# power.net
KiCad netlist of a schematic drawn in EAGLE
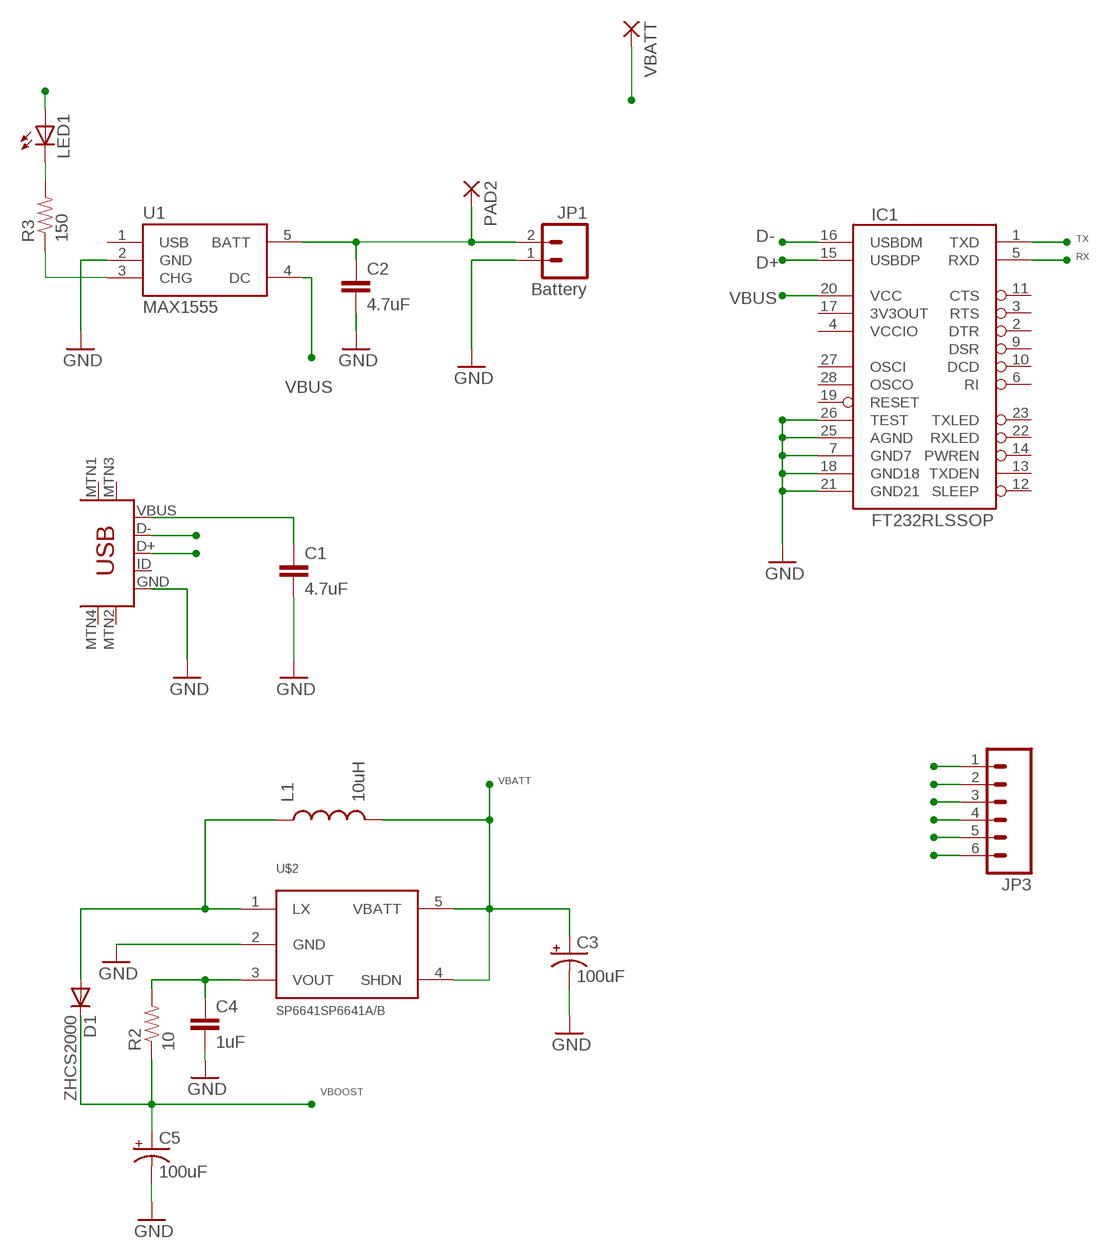
[diagram p0: schematic, sheet 1]

(export (version "E")
  (design (tool "Eeschema 10.0.6"))
  (components
    (comp (ref "C1")
      (value "4.7uF")
      (footprint "eagle-import:1206")
      (libsource (lib "eagle-import") (part "CAP1206"))
    )
    (comp (ref "C2")
      (value "4.7uF")
      (footprint "eagle-import:1206")
      (libsource (lib "eagle-import") (part "CAP1206"))
    )
    (comp (ref "C3")
      (value "100uF")
      (footprint "eagle-import:PANASONIC_D")
      (libsource (lib "eagle-import") (part "CPOL-USD"))
    )
    (comp (ref "C4")
      (value "1uF")
      (footprint "eagle-import:0805")
      (libsource (lib "eagle-import") (part "CAP0805"))
    )
    (comp (ref "C5")
      (value "100uF")
      (footprint "eagle-import:PANASONIC_D")
      (libsource (lib "eagle-import") (part "CPOL-USD"))
    )
    (comp (ref "D1")
      (value "ZHCS2000")
      (footprint "eagle-import:SMB-DIODE")
      (libsource (lib "eagle-import") (part "DIODESMB"))
    )
    (comp (ref "IC1")
      (value "FT232RLSSOP")
      (footprint "eagle-import:SSOP28DB")
      (libsource (lib "eagle-import") (part "FT232RLSSOP"))
    )
    (comp (ref "JP1")
      (value "Battery")
      (footprint "eagle-import:JST-2-SMD")
      (libsource (lib "eagle-import") (part "M02-JST-2MM-SMT"))
    )
    (comp (ref "JP3")
      (value "M06SMD")
      (footprint "eagle-import:1X06-SMD")
      (libsource (lib "eagle-import") (part "M06SMD"))
    )
    (comp (ref "L1")
      (value "10uH")
      (footprint "eagle-import:CR54")
      (libsource (lib "eagle-import") (part "INDUCTORCR54"))
    )
    (comp (ref "LED1")
      (value "LED0603")
      (footprint "eagle-import:LED-0603")
      (libsource (lib "eagle-import") (part "LED0603"))
    )
    (comp (ref "PAD2")
      (value "WIREPAD2,54/1,0")
      (footprint "eagle-import:2,54_1,0")
      (libsource (lib "eagle-import") (part "WIREPAD2,54/1,0"))
    )
    (comp (ref "R2")
      (value "10")
      (footprint "eagle-import:0603-RES")
      (libsource (lib "eagle-import") (part "RESISTOR0603-RES"))
    )
    (comp (ref "R3")
      (value "150")
      (footprint "eagle-import:0603-RES")
      (libsource (lib "eagle-import") (part "RESISTOR0603-RES"))
    )
    (comp (ref "U$1")
      (value "USB-MINIB-5PIN")
      (footprint "eagle-import:USB-MINIB")
      (libsource (lib "eagle-import") (part "USB-MINIB-5PIN"))
    )
    (comp (ref "U$2")
      (value "SP6641SP6641A/B")
      (footprint "eagle-import:SOT23-5")
      (libsource (lib "eagle-import") (part "SP6641SP6641A/B"))
    )
    (comp (ref "U1")
      (value "MAX1555")
      (footprint "eagle-import:SOT23-5")
      (libsource (lib "eagle-import") (part "MAX1555"))
    )
    (comp (ref "VBATT")
      (value "WIREPAD2,54/1,0")
      (footprint "eagle-import:2,54_1,0")
      (libsource (lib "eagle-import") (part "WIREPAD2,54/1,0"))
    )
  )
  (nets
    (net (code "1") (name "/D+") (class "Default")
      (node (ref "IC1") (pin "15") (pinfunction "USBDP_15") (pintype "bidirectional"))
      (node (ref "U$1") (pin "D+") (pinfunction "D+_D+") (pintype "bidirectional"))
    )
    (net (code "2") (name "/D-") (class "Default")
      (node (ref "IC1") (pin "16") (pinfunction "USBDM_16") (pintype "bidirectional"))
      (node (ref "U$1") (pin "D-") (pinfunction "D-_D-") (pintype "bidirectional"))
    )
    (net (code "3") (name "/RX") (class "Default")
      (node (ref "IC1") (pin "5") (pinfunction "RXD_5") (pintype "input"))
      (node (ref "JP3") (pin "1") (pinfunction "1_1") (pintype "passive"))
    )
    (net (code "4") (name "/TX") (class "Default")
      (node (ref "IC1") (pin "1") (pinfunction "TXD_1") (pintype "output"))
      (node (ref "JP3") (pin "2") (pinfunction "2_2") (pintype "passive"))
    )
    (net (code "5") (name "/VBATT") (class "Default")
      (node (ref "C3") (pin "+") (pinfunction "+_+") (pintype "passive"))
      (node (ref "JP3") (pin "5") (pinfunction "5_5") (pintype "passive"))
      (node (ref "L1") (pin "P$2") (pinfunction "2_P$2") (pintype "passive"))
      (node (ref "U$2") (pin "4") (pinfunction "SHDN_4") (pintype "bidirectional"))
      (node (ref "U$2") (pin "5") (pinfunction "VBATT_5") (pintype "bidirectional"))
      (node (ref "VBATT") (pin "1") (pinfunction "P_1") (pintype "passive"))
    )
    (net (code "6") (name "/VBOOST") (class "Default")
      (node (ref "C5") (pin "+") (pinfunction "+_+") (pintype "passive"))
      (node (ref "D1") (pin "C") (pinfunction "C_C") (pintype "passive"))
      (node (ref "JP3") (pin "4") (pinfunction "4_4") (pintype "passive"))
      (node (ref "R2") (pin "1") (pinfunction "1_1") (pintype "passive"))
    )
    (net (code "7") (name "/VBUS") (class "Default")
      (node (ref "C1") (pin "1") (pinfunction "1_1") (pintype "passive"))
      (node (ref "IC1") (pin "20") (pinfunction "VCC_20") (pintype "power_in"))
      (node (ref "JP3") (pin "3") (pinfunction "3_3") (pintype "passive"))
      (node (ref "LED1") (pin "A") (pinfunction "A_A") (pintype "passive"))
      (node (ref "U$1") (pin "VBUS") (pinfunction "VBUS_VBUS") (pintype "bidirectional"))
      (node (ref "U1") (pin "4") (pinfunction "DC_4") (pintype "bidirectional"))
    )
    (net (code "8") (name "/VCCIO") (class "Default")
      (node (ref "IC1") (pin "4") (pinfunction "VCCIO_4") (pintype "power_in"))
    )
    (net (code "9") (name "GND") (class "Default")
      (node (ref "C1") (pin "2") (pinfunction "2_2") (pintype "passive"))
      (node (ref "C2") (pin "2") (pinfunction "2_2") (pintype "passive"))
      (node (ref "C3") (pin "-") (pinfunction "-_-") (pintype "passive"))
      (node (ref "C4") (pin "2") (pinfunction "2_2") (pintype "passive"))
      (node (ref "C5") (pin "-") (pinfunction "-_-") (pintype "passive"))
      (node (ref "IC1") (pin "18") (pinfunction "GND18_18") (pintype "power_in"))
      (node (ref "IC1") (pin "21") (pinfunction "GND21_21") (pintype "power_in"))
      (node (ref "IC1") (pin "25") (pinfunction "AGND_25") (pintype "power_in"))
      (node (ref "IC1") (pin "26") (pinfunction "TEST_26") (pintype "input"))
      (node (ref "IC1") (pin "7") (pinfunction "GND7_7") (pintype "power_in"))
      (node (ref "JP1") (pin "1") (pinfunction "1_1") (pintype "passive"))
      (node (ref "JP3") (pin "6") (pinfunction "6_6") (pintype "passive"))
      (node (ref "U$1") (pin "GND") (pinfunction "GND_GND") (pintype "bidirectional"))
      (node (ref "U$2") (pin "2") (pinfunction "GND_2") (pintype "bidirectional"))
      (node (ref "U1") (pin "2") (pinfunction "GND_2") (pintype "bidirectional"))
    )
    (net (code "10") (name "Net-(L1-1)") (class "Default")
      (node (ref "D1") (pin "A") (pinfunction "A_A") (pintype "passive"))
      (node (ref "L1") (pin "P$1") (pinfunction "1_P$1") (pintype "passive"))
      (node (ref "U$2") (pin "1") (pinfunction "LX_1") (pintype "bidirectional"))
    )
    (net (code "11") (name "Net-(LED1-PadC)") (class "Default")
      (node (ref "LED1") (pin "C") (pinfunction "C_C") (pintype "passive"))
      (node (ref "R3") (pin "2") (pinfunction "2_2") (pintype "passive"))
    )
    (net (code "12") (name "Net-(PAD2-P)") (class "Default")
      (node (ref "C2") (pin "1") (pinfunction "1_1") (pintype "passive"))
      (node (ref "JP1") (pin "2") (pinfunction "2_2") (pintype "passive"))
      (node (ref "PAD2") (pin "1") (pinfunction "P_1") (pintype "passive"))
      (node (ref "U1") (pin "5") (pinfunction "BATT_5") (pintype "bidirectional"))
    )
    (net (code "13") (name "Net-(U$2-VOUT)") (class "Default")
      (node (ref "C4") (pin "1") (pinfunction "1_1") (pintype "passive"))
      (node (ref "R2") (pin "2") (pinfunction "2_2") (pintype "passive"))
      (node (ref "U$2") (pin "3") (pinfunction "VOUT_3") (pintype "bidirectional"))
    )
    (net (code "14") (name "Net-(U1-CHG)") (class "Default")
      (node (ref "R3") (pin "1") (pinfunction "1_1") (pintype "passive"))
      (node (ref "U1") (pin "3") (pinfunction "CHG_3") (pintype "bidirectional"))
    )
    (net (code "15") (name "unconnected-(IC1-3V3OUT-Pad17)") (class "Default")
      (node (ref "IC1") (pin "17") (pinfunction "3V3OUT_17") (pintype "output"))
    )
    (net (code "16") (name "unconnected-(IC1-CTS-Pad11)") (class "Default")
      (node (ref "IC1") (pin "11") (pinfunction "CTS_11") (pintype "input"))
    )
    (net (code "17") (name "unconnected-(IC1-DCD-Pad10)") (class "Default")
      (node (ref "IC1") (pin "10") (pinfunction "DCD_10") (pintype "input"))
    )
    (net (code "18") (name "unconnected-(IC1-DSR-Pad9)") (class "Default")
      (node (ref "IC1") (pin "9") (pinfunction "DSR_9") (pintype "input"))
    )
    (net (code "19") (name "unconnected-(IC1-DTR-Pad2)") (class "Default")
      (node (ref "IC1") (pin "2") (pinfunction "DTR_2") (pintype "output"))
    )
    (net (code "20") (name "unconnected-(IC1-OSCI-Pad27)") (class "Default")
      (node (ref "IC1") (pin "27") (pinfunction "OSCI_27") (pintype "input"))
    )
    (net (code "21") (name "unconnected-(IC1-OSCO-Pad28)") (class "Default")
      (node (ref "IC1") (pin "28") (pinfunction "OSCO_28") (pintype "output"))
    )
    (net (code "22") (name "unconnected-(IC1-PWREN-Pad14)") (class "Default")
      (node (ref "IC1") (pin "14") (pinfunction "PWREN_14") (pintype "input"))
    )
    (net (code "23") (name "unconnected-(IC1-RESET-Pad19)") (class "Default")
      (node (ref "IC1") (pin "19") (pinfunction "RESET_19") (pintype "input"))
    )
    (net (code "24") (name "unconnected-(IC1-RI-Pad6)") (class "Default")
      (node (ref "IC1") (pin "6") (pinfunction "RI_6") (pintype "input"))
    )
    (net (code "25") (name "unconnected-(IC1-RTS-Pad3)") (class "Default")
      (node (ref "IC1") (pin "3") (pinfunction "RTS_3") (pintype "output"))
    )
    (net (code "26") (name "unconnected-(IC1-RXLED-Pad22)") (class "Default")
      (node (ref "IC1") (pin "22") (pinfunction "RXLED_22") (pintype "input"))
    )
    (net (code "27") (name "unconnected-(IC1-SLEEP-Pad12)") (class "Default")
      (node (ref "IC1") (pin "12") (pinfunction "SLEEP_12") (pintype "input"))
    )
    (net (code "28") (name "unconnected-(IC1-TXDEN-Pad13)") (class "Default")
      (node (ref "IC1") (pin "13") (pinfunction "TXDEN_13") (pintype "input"))
    )
    (net (code "29") (name "unconnected-(IC1-TXLED-Pad23)") (class "Default")
      (node (ref "IC1") (pin "23") (pinfunction "TXLED_23") (pintype "input"))
    )
    (net (code "30") (name "unconnected-(U$1-MTN1-PadMTN3)") (class "Default")
      (node (ref "U$1") (pin "MTN3") (pinfunction "MTN1_MTN3") (pintype "bidirectional"))
    )
    (net (code "31") (name "unconnected-(U$1-MTN2-PadMTN1)") (class "Default")
      (node (ref "U$1") (pin "MTN1") (pinfunction "MTN2_MTN1") (pintype "bidirectional"))
    )
    (net (code "32") (name "unconnected-(U$1-MTN3-PadMTN2)") (class "Default")
      (node (ref "U$1") (pin "MTN2") (pinfunction "MTN3_MTN2") (pintype "bidirectional"))
    )
    (net (code "33") (name "unconnected-(U$1-PadID)") (class "Default")
      (node (ref "U$1") (pin "ID") (pinfunction "ID_ID") (pintype "bidirectional"))
    )
    (net (code "34") (name "unconnected-(U$1-PadMTN4)") (class "Default")
      (node (ref "U$1") (pin "MTN4") (pinfunction "MTN4_MTN4") (pintype "bidirectional"))
    )
    (net (code "35") (name "unconnected-(U1-USB-Pad1)") (class "Default")
      (node (ref "U1") (pin "1") (pinfunction "USB_1") (pintype "bidirectional"))
    )
  )
)
